# esp32.net
KiCad netlist of a schematic drawn in EAGLE
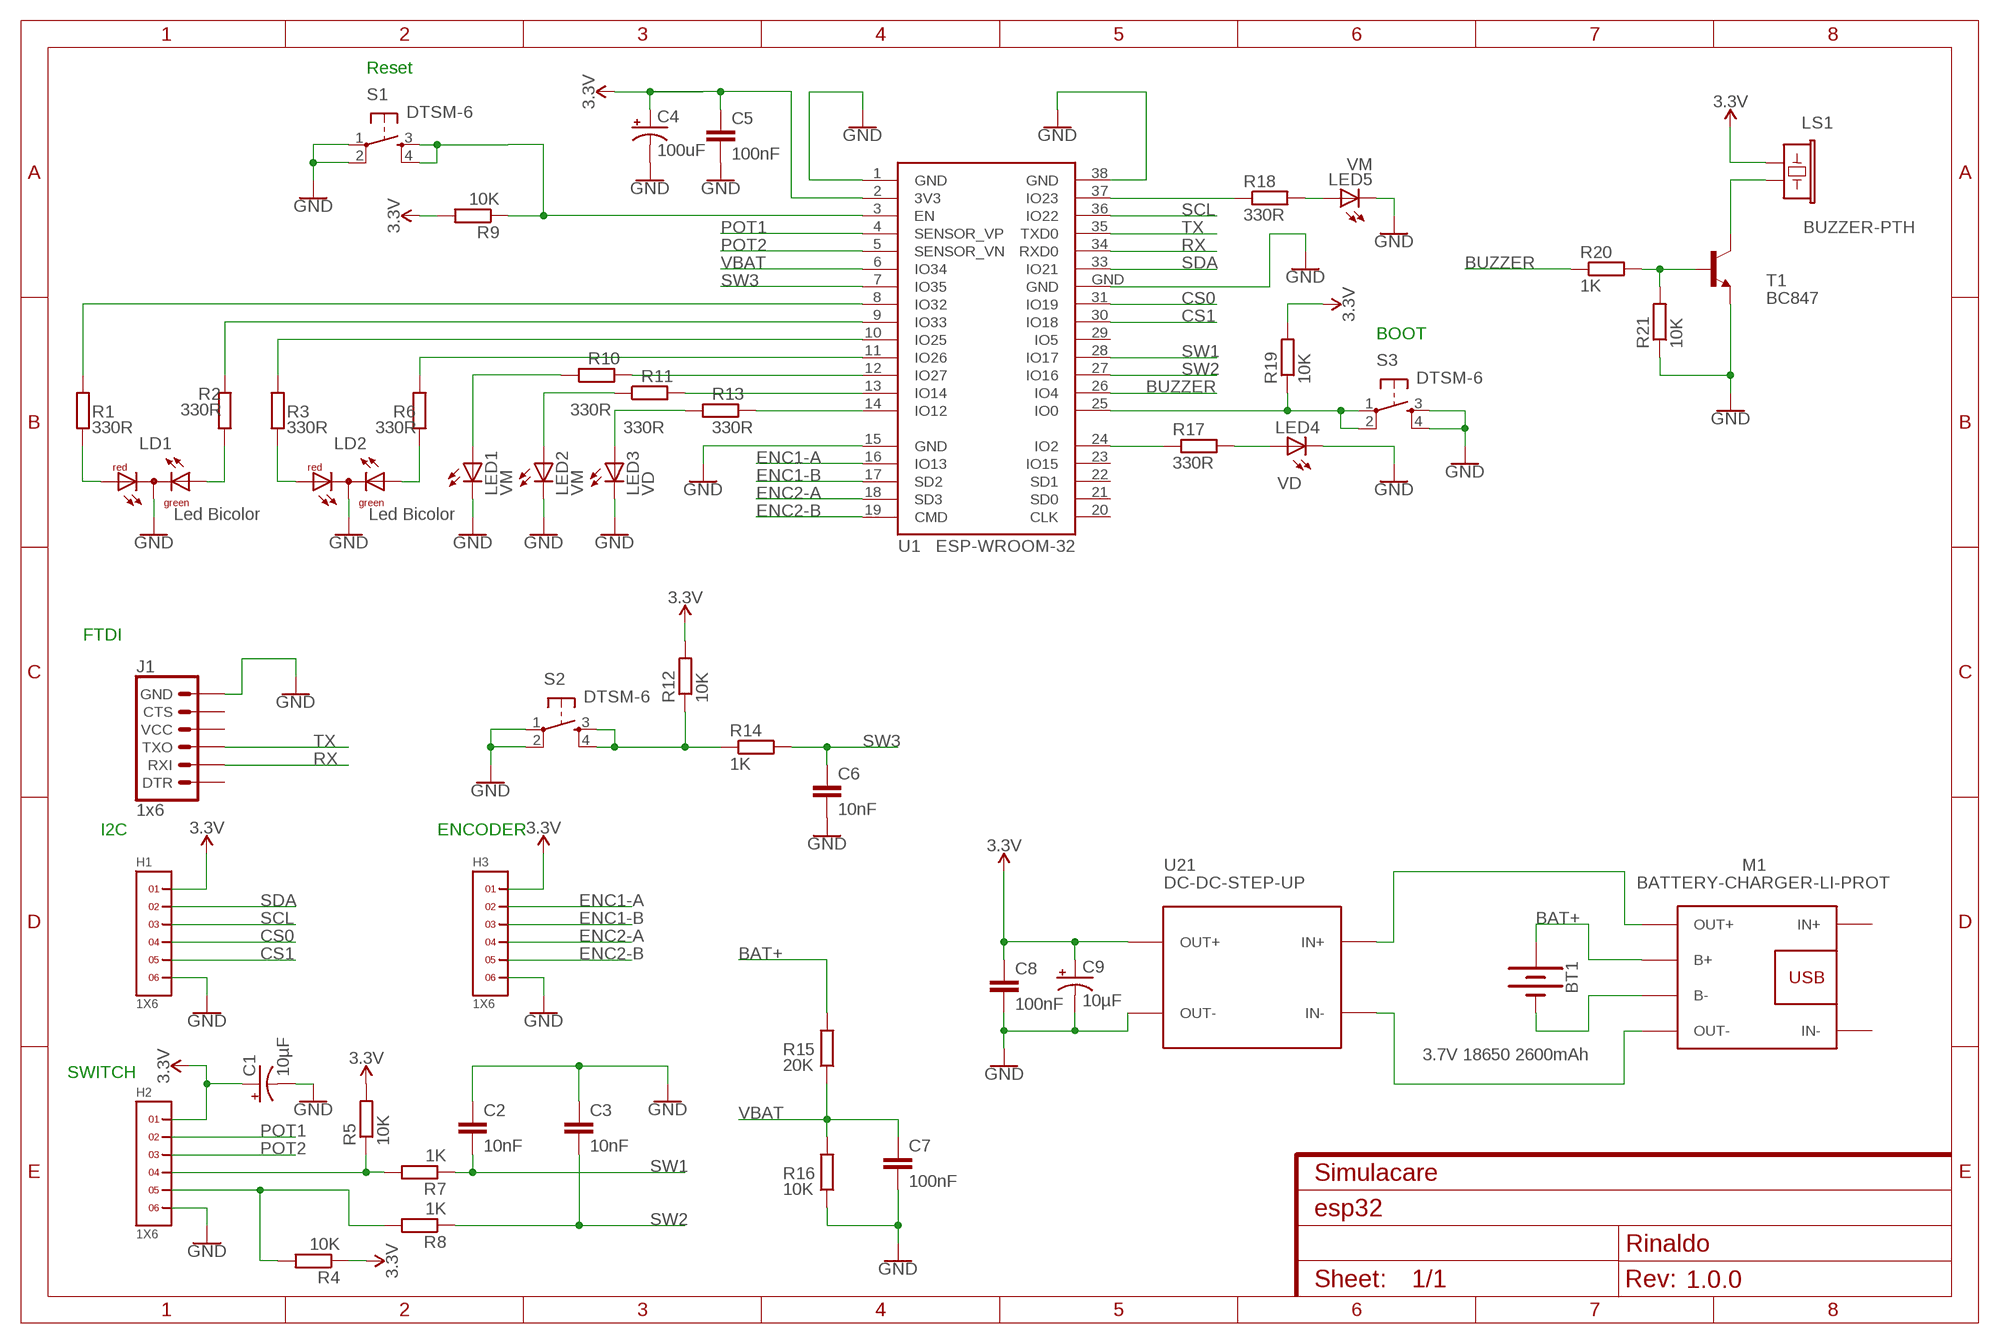
[diagram p0: schematic, sheet 1]

(export (version "E")
  (design (tool "Eeschema 10.0.6"))
  (components
    (comp (ref "BT1")
      (value "3.7V 18650 2600mAh")
      (footprint "eagle-import:BATTERY_18650-HOLDER")
      (libsource (lib "eagle-import") (part "BATTERY-18650"))
    )
    (comp (ref "C1")
      (value "10µF")
      (footprint "eagle-import:EIA6032-NOM")
      (libsource (lib "eagle-import") (part "10UF-POLAR-EIA6032-25V-10%"))
    )
    (comp (ref "C2")
      (value "10nF")
      (footprint "eagle-import:0603")
      (libsource (lib "eagle-import") (part "0.1UF-0603-25V-5%"))
    )
    (comp (ref "C3")
      (value "10nF")
      (footprint "eagle-import:0603")
      (libsource (lib "eagle-import") (part "0.1UF-0603-25V-5%"))
    )
    (comp (ref "C4")
      (value "100uF")
      (footprint "eagle-import:NIC_10X10.5_CAP")
      (libsource (lib "eagle-import") (part "100UF-POLAR-10X10.5-63V-20%"))
    )
    (comp (ref "C5")
      (value "100nF")
      (footprint "eagle-import:0603")
      (libsource (lib "eagle-import") (part "0.1UF-0603-25V-5%"))
    )
    (comp (ref "C6")
      (value "10nF")
      (footprint "eagle-import:0603")
      (libsource (lib "eagle-import") (part "0.1UF-0603-25V-5%"))
    )
    (comp (ref "C7")
      (value "100nF")
      (footprint "eagle-import:0603")
      (libsource (lib "eagle-import") (part "0.1UF-0603-25V-5%"))
    )
    (comp (ref "C8")
      (value "100nF")
      (footprint "eagle-import:0603")
      (libsource (lib "eagle-import") (part "0.1UF-0603-25V-5%"))
    )
    (comp (ref "C9")
      (value "10µF")
      (footprint "eagle-import:EIA6032-NOM")
      (libsource (lib "eagle-import") (part "10UF-POLAR-EIA6032-25V-10%"))
    )
    (comp (ref "H1")
      (value "1X6")
      (footprint "eagle-import:1X6")
      (libsource (lib "eagle-import") (part "1X6"))
    )
    (comp (ref "H2")
      (value "1X6")
      (footprint "eagle-import:1X6")
      (libsource (lib "eagle-import") (part "1X6"))
    )
    (comp (ref "H3")
      (value "1X6")
      (footprint "eagle-import:1X6")
      (libsource (lib "eagle-import") (part "1X6"))
    )
    (comp (ref "J1")
      (value "1x6")
      (footprint "eagle-import:6_PIN_SERIAL_TARGET_SIDE_W_SILK")
      (libsource (lib "eagle-import") (part "6_PIN_SERIAL_TARGETSILK"))
    )
    (comp (ref "LD1")
      (value "Led Bicolor")
      (footprint "eagle-import:DUOLED-C-5MM")
      (libsource (lib "eagle-import") (part "DUOLED-RG-C"))
    )
    (comp (ref "LD2")
      (value "Led Bicolor")
      (footprint "eagle-import:DUOLED-C-5MM")
      (libsource (lib "eagle-import") (part "DUOLED-RG-C"))
    )
    (comp (ref "LED1")
      (value "VM")
      (footprint "eagle-import:LED5MM")
      (libsource (lib "eagle-import") (part "LED5MM"))
    )
    (comp (ref "LED2")
      (value "VM")
      (footprint "eagle-import:LED5MM")
      (libsource (lib "eagle-import") (part "LED5MM"))
    )
    (comp (ref "LED3")
      (value "VD")
      (footprint "eagle-import:LED5MM")
      (libsource (lib "eagle-import") (part "LED5MM"))
    )
    (comp (ref "LED4")
      (value "VD")
      (footprint "eagle-import:LED5MM")
      (libsource (lib "eagle-import") (part "LED5MM"))
    )
    (comp (ref "LED5")
      (value "VM")
      (footprint "eagle-import:LED5MM")
      (libsource (lib "eagle-import") (part "LED5MM"))
    )
    (comp (ref "LS1")
      (value "BUZZER-PTH")
      (footprint "eagle-import:BUZZER-12MM")
      (libsource (lib "eagle-import") (part "BUZZER-PTH"))
    )
    (comp (ref "M1")
      (value "BATTERY-CHARGER-LI-PROT")
      (footprint "eagle-import:BATTERY-CHARGER-LI-PROT")
      (libsource (lib "eagle-import") (part "BATTERY-CHARGER-LI-PROT"))
    )
    (comp (ref "R1")
      (value "330R")
      (footprint "eagle-import:R0603")
      (libsource (lib "eagle-import") (part "R-EU_R0603"))
    )
    (comp (ref "R2")
      (value "330R")
      (footprint "eagle-import:R0603")
      (libsource (lib "eagle-import") (part "R-EU_R0603"))
    )
    (comp (ref "R3")
      (value "330R")
      (footprint "eagle-import:R0603")
      (libsource (lib "eagle-import") (part "R-EU_R0603"))
    )
    (comp (ref "R4")
      (value "10K")
      (footprint "eagle-import:R0603")
      (libsource (lib "eagle-import") (part "R-EU_R0603"))
    )
    (comp (ref "R5")
      (value "10K")
      (footprint "eagle-import:R0603")
      (libsource (lib "eagle-import") (part "R-EU_R0603"))
    )
    (comp (ref "R6")
      (value "330R")
      (footprint "eagle-import:R0603")
      (libsource (lib "eagle-import") (part "R-EU_R0603"))
    )
    (comp (ref "R7")
      (value "1K")
      (footprint "eagle-import:R0603")
      (libsource (lib "eagle-import") (part "R-EU_R0603"))
    )
    (comp (ref "R8")
      (value "1K")
      (footprint "eagle-import:R0603")
      (libsource (lib "eagle-import") (part "R-EU_R0603"))
    )
    (comp (ref "R9")
      (value "10K")
      (footprint "eagle-import:R0603")
      (libsource (lib "eagle-import") (part "R-EU_R0603"))
    )
    (comp (ref "R10")
      (value "330R")
      (footprint "eagle-import:R0603")
      (libsource (lib "eagle-import") (part "R-EU_R0603"))
    )
    (comp (ref "R11")
      (value "330R")
      (footprint "eagle-import:R0603")
      (libsource (lib "eagle-import") (part "R-EU_R0603"))
    )
    (comp (ref "R12")
      (value "10K")
      (footprint "eagle-import:R0603")
      (libsource (lib "eagle-import") (part "R-EU_R0603"))
    )
    (comp (ref "R13")
      (value "330R")
      (footprint "eagle-import:R0603")
      (libsource (lib "eagle-import") (part "R-EU_R0603"))
    )
    (comp (ref "R14")
      (value "1K")
      (footprint "eagle-import:R0603")
      (libsource (lib "eagle-import") (part "R-EU_R0603"))
    )
    (comp (ref "R15")
      (value "20K")
      (footprint "eagle-import:R0603")
      (libsource (lib "eagle-import") (part "R-EU_R0603"))
    )
    (comp (ref "R16")
      (value "10K")
      (footprint "eagle-import:R0603")
      (libsource (lib "eagle-import") (part "R-EU_R0603"))
    )
    (comp (ref "R17")
      (value "330R")
      (footprint "eagle-import:R0603")
      (libsource (lib "eagle-import") (part "R-EU_R0603"))
    )
    (comp (ref "R18")
      (value "330R")
      (footprint "eagle-import:R0603")
      (libsource (lib "eagle-import") (part "R-EU_R0603"))
    )
    (comp (ref "R19")
      (value "10K")
      (footprint "eagle-import:R0603")
      (libsource (lib "eagle-import") (part "R-EU_R0603"))
    )
    (comp (ref "R20")
      (value "1K")
      (footprint "eagle-import:R0603")
      (libsource (lib "eagle-import") (part "R-EU_R0603"))
    )
    (comp (ref "R21")
      (value "10K")
      (footprint "eagle-import:R0603")
      (libsource (lib "eagle-import") (part "R-EU_R0603"))
    )
    (comp (ref "S1")
      (value "DTSM-6")
      (footprint "eagle-import:DTSM-6")
      (libsource (lib "eagle-import") (part "DTSM-6"))
    )
    (comp (ref "S2")
      (value "DTSM-6")
      (footprint "eagle-import:DTSM-6")
      (libsource (lib "eagle-import") (part "DTSM-6"))
    )
    (comp (ref "S3")
      (value "DTSM-6")
      (footprint "eagle-import:DTSM-6")
      (libsource (lib "eagle-import") (part "DTSM-6"))
    )
    (comp (ref "T1")
      (value "BC847")
      (footprint "eagle-import:SOT23")
      (libsource (lib "eagle-import") (part "BC847"))
    )
    (comp (ref "U1")
      (value "ESP-WROOM-32")
      (footprint "eagle-import:ESP-WROOM-32")
      (libsource (lib "eagle-import") (part "ESP-WROOM-32"))
    )
    (comp (ref "U21")
      (value "DC-DC-STEP-UP")
      (footprint "eagle-import:DC-DC-STEP-UP-MT3608")
      (libsource (lib "eagle-import") (part "DC-DC-STEP-UP-MT3608"))
    )
  )
  (nets
    (net (code "1") (name "/BAT+") (class "Default")
      (node (ref "BT1") (pin "PWR@1") (pinfunction "+_PWR@1") (pintype "power_in"))
      (node (ref "M1") (pin "B+") (pinfunction "B+_B+") (pintype "bidirectional"))
      (node (ref "R15") (pin "2") (pinfunction "2_2") (pintype "passive"))
    )
    (net (code "2") (name "/BUZZER") (class "Default")
      (node (ref "R20") (pin "1") (pinfunction "1_1") (pintype "passive"))
      (node (ref "U1") (pin "26") (pinfunction "IO4_26") (pintype "bidirectional"))
    )
    (net (code "3") (name "/CS0") (class "Default")
      (node (ref "H1") (pin "4") (pinfunction "4_4") (pintype "bidirectional"))
      (node (ref "U1") (pin "31") (pinfunction "IO19_31") (pintype "bidirectional"))
    )
    (net (code "4") (name "/CS1") (class "Default")
      (node (ref "H1") (pin "5") (pinfunction "5_5") (pintype "bidirectional"))
      (node (ref "U1") (pin "30") (pinfunction "IO18_30") (pintype "bidirectional"))
    )
    (net (code "5") (name "/ENC1-A") (class "Default")
      (node (ref "H3") (pin "2") (pinfunction "2_2") (pintype "bidirectional"))
      (node (ref "U1") (pin "16") (pinfunction "IO13_16") (pintype "bidirectional"))
    )
    (net (code "6") (name "/ENC1-B") (class "Default")
      (node (ref "H3") (pin "3") (pinfunction "3_3") (pintype "bidirectional"))
      (node (ref "U1") (pin "17") (pinfunction "SD2_17") (pintype "bidirectional"))
    )
    (net (code "7") (name "/ENC2-A") (class "Default")
      (node (ref "H3") (pin "4") (pinfunction "4_4") (pintype "bidirectional"))
      (node (ref "U1") (pin "18") (pinfunction "SD3_18") (pintype "bidirectional"))
    )
    (net (code "8") (name "/ENC2-B") (class "Default")
      (node (ref "H3") (pin "5") (pinfunction "5_5") (pintype "bidirectional"))
      (node (ref "U1") (pin "19") (pinfunction "CMD_19") (pintype "bidirectional"))
    )
    (net (code "9") (name "/POT1") (class "Default")
      (node (ref "H2") (pin "2") (pinfunction "2_2") (pintype "bidirectional"))
      (node (ref "U1") (pin "4") (pinfunction "SENSOR_VP_4") (pintype "bidirectional"))
    )
    (net (code "10") (name "/POT2") (class "Default")
      (node (ref "H2") (pin "3") (pinfunction "3_3") (pintype "bidirectional"))
      (node (ref "U1") (pin "5") (pinfunction "SENSOR_VN_5") (pintype "bidirectional"))
    )
    (net (code "11") (name "/RX") (class "Default")
      (node (ref "J1") (pin "P$3") (pinfunction "RXI_P$3") (pintype "passive"))
      (node (ref "U1") (pin "34") (pinfunction "RXD0_34") (pintype "bidirectional"))
    )
    (net (code "12") (name "/SCL") (class "Default")
      (node (ref "H1") (pin "3") (pinfunction "3_3") (pintype "bidirectional"))
      (node (ref "U1") (pin "36") (pinfunction "IO22_36") (pintype "bidirectional"))
    )
    (net (code "13") (name "/SDA") (class "Default")
      (node (ref "H1") (pin "2") (pinfunction "2_2") (pintype "bidirectional"))
      (node (ref "U1") (pin "33") (pinfunction "IO21_33") (pintype "bidirectional"))
    )
    (net (code "14") (name "/SW1") (class "Default")
      (node (ref "C2") (pin "2") (pinfunction "2_2") (pintype "passive"))
      (node (ref "R7") (pin "1") (pinfunction "1_1") (pintype "passive"))
      (node (ref "U1") (pin "28") (pinfunction "IO17_28") (pintype "bidirectional"))
    )
    (net (code "15") (name "/SW2") (class "Default")
      (node (ref "C3") (pin "2") (pinfunction "2_2") (pintype "passive"))
      (node (ref "R8") (pin "1") (pinfunction "1_1") (pintype "passive"))
      (node (ref "U1") (pin "27") (pinfunction "IO16_27") (pintype "bidirectional"))
    )
    (net (code "16") (name "/SW3") (class "Default")
      (node (ref "C6") (pin "1") (pinfunction "1_1") (pintype "passive"))
      (node (ref "R14") (pin "2") (pinfunction "2_2") (pintype "passive"))
      (node (ref "U1") (pin "7") (pinfunction "IO35_7") (pintype "bidirectional"))
    )
    (net (code "17") (name "/TX") (class "Default")
      (node (ref "J1") (pin "P$2") (pinfunction "TXO_P$2") (pintype "passive"))
      (node (ref "U1") (pin "35") (pinfunction "TXD0_35") (pintype "bidirectional"))
    )
    (net (code "18") (name "/VBAT") (class "Default")
      (node (ref "C7") (pin "1") (pinfunction "1_1") (pintype "passive"))
      (node (ref "R15") (pin "1") (pinfunction "1_1") (pintype "passive"))
      (node (ref "R16") (pin "2") (pinfunction "2_2") (pintype "passive"))
      (node (ref "U1") (pin "6") (pinfunction "IO34_6") (pintype "bidirectional"))
    )
    (net (code "19") (name "3.3V") (class "Default")
      (node (ref "C1") (pin "A") (pinfunction "+_A") (pintype "passive"))
      (node (ref "C4") (pin "+") (pinfunction "+_+") (pintype "passive"))
      (node (ref "C5") (pin "1") (pinfunction "1_1") (pintype "passive"))
      (node (ref "C8") (pin "1") (pinfunction "1_1") (pintype "passive"))
      (node (ref "C9") (pin "A") (pinfunction "+_A") (pintype "passive"))
      (node (ref "H1") (pin "1") (pinfunction "1_1") (pintype "bidirectional"))
      (node (ref "H2") (pin "1") (pinfunction "1_1") (pintype "bidirectional"))
      (node (ref "H3") (pin "1") (pinfunction "1_1") (pintype "bidirectional"))
      (node (ref "LS1") (pin "+") (pinfunction "1_+") (pintype "passive"))
      (node (ref "R12") (pin "2") (pinfunction "2_2") (pintype "passive"))
      (node (ref "R19") (pin "2") (pinfunction "2_2") (pintype "passive"))
      (node (ref "R4") (pin "1") (pinfunction "1_1") (pintype "passive"))
      (node (ref "R5") (pin "2") (pinfunction "2_2") (pintype "passive"))
      (node (ref "R9") (pin "2") (pinfunction "2_2") (pintype "passive"))
      (node (ref "U1") (pin "2") (pinfunction "3V3_2") (pintype "power_in"))
      (node (ref "U21") (pin "OUT+") (pinfunction "OUT+_OUT+") (pintype "bidirectional"))
    )
    (net (code "20") (name "GND") (class "Default")
      (node (ref "C1") (pin "C") (pinfunction "-_C") (pintype "passive"))
      (node (ref "C2") (pin "1") (pinfunction "1_1") (pintype "passive"))
      (node (ref "C3") (pin "1") (pinfunction "1_1") (pintype "passive"))
      (node (ref "C4") (pin "-") (pinfunction "-_-") (pintype "passive"))
      (node (ref "C5") (pin "2") (pinfunction "2_2") (pintype "passive"))
      (node (ref "C6") (pin "2") (pinfunction "2_2") (pintype "passive"))
      (node (ref "C7") (pin "2") (pinfunction "2_2") (pintype "passive"))
      (node (ref "C8") (pin "2") (pinfunction "2_2") (pintype "passive"))
      (node (ref "C9") (pin "C") (pinfunction "-_C") (pintype "passive"))
      (node (ref "H1") (pin "6") (pinfunction "6_6") (pintype "bidirectional"))
      (node (ref "H2") (pin "6") (pinfunction "6_6") (pintype "bidirectional"))
      (node (ref "H3") (pin "6") (pinfunction "6_6") (pintype "bidirectional"))
      (node (ref "J1") (pin "P$6") (pinfunction "GND_P$6") (pintype "passive"))
      (node (ref "LD1") (pin "C") (pinfunction "C_C") (pintype "passive"))
      (node (ref "LD2") (pin "C") (pinfunction "C_C") (pintype "passive"))
      (node (ref "LED1") (pin "K") (pinfunction "C_K") (pintype "passive"))
      (node (ref "LED2") (pin "K") (pinfunction "C_K") (pintype "passive"))
      (node (ref "LED3") (pin "K") (pinfunction "C_K") (pintype "passive"))
      (node (ref "LED4") (pin "K") (pinfunction "C_K") (pintype "passive"))
      (node (ref "LED5") (pin "K") (pinfunction "C_K") (pintype "passive"))
      (node (ref "R16") (pin "1") (pinfunction "1_1") (pintype "passive"))
      (node (ref "R21") (pin "1") (pinfunction "1_1") (pintype "passive"))
      (node (ref "S1") (pin "1") (pinfunction "1_1") (pintype "passive"))
      (node (ref "S1") (pin "2") (pinfunction "2_2") (pintype "passive"))
      (node (ref "S2") (pin "1") (pinfunction "1_1") (pintype "passive"))
      (node (ref "S2") (pin "2") (pinfunction "2_2") (pintype "passive"))
      (node (ref "S3") (pin "3") (pinfunction "3_3") (pintype "passive"))
      (node (ref "S3") (pin "4") (pinfunction "4_4") (pintype "passive"))
      (node (ref "T1") (pin "2") (pinfunction "E_2") (pintype "passive"))
      (node (ref "U1") (pin "1") (pinfunction "GND_1") (pintype "power_in"))
      (node (ref "U1") (pin "15") (pinfunction "GND_15") (pintype "power_in"))
      (node (ref "U1") (pin "38") (pinfunction "GND_38") (pintype "power_in"))
      (node (ref "U1") (pin "GND") (pinfunction "GND_GND") (pintype "power_in"))
      (node (ref "U21") (pin "OUT-") (pinfunction "OUT-_OUT-") (pintype "bidirectional"))
    )
    (net (code "21") (name "Net-(BT1--)") (class "Default")
      (node (ref "BT1") (pin "GND@1") (pinfunction "-_GND@1") (pintype "power_in"))
      (node (ref "M1") (pin "B-") (pinfunction "B-_B-") (pintype "bidirectional"))
    )
    (net (code "22") (name "Net-(H2-Pad4)") (class "Default")
      (node (ref "H2") (pin "4") (pinfunction "4_4") (pintype "bidirectional"))
      (node (ref "R5") (pin "1") (pinfunction "1_1") (pintype "passive"))
      (node (ref "R7") (pin "2") (pinfunction "2_2") (pintype "passive"))
    )
    (net (code "23") (name "Net-(H2-Pad5)") (class "Default")
      (node (ref "H2") (pin "5") (pinfunction "5_5") (pintype "bidirectional"))
      (node (ref "R4") (pin "2") (pinfunction "2_2") (pintype "passive"))
      (node (ref "R8") (pin "2") (pinfunction "2_2") (pintype "passive"))
    )
    (net (code "24") (name "Net-(LD1-AG)") (class "Default")
      (node (ref "LD1") (pin "AX") (pinfunction "AG_AX") (pintype "passive"))
      (node (ref "R2") (pin "1") (pinfunction "1_1") (pintype "passive"))
    )
    (net (code "25") (name "Net-(LD1-PadAR)") (class "Default")
      (node (ref "LD1") (pin "AR") (pinfunction "AR_AR") (pintype "passive"))
      (node (ref "R1") (pin "1") (pinfunction "1_1") (pintype "passive"))
    )
    (net (code "26") (name "Net-(LD2-AG)") (class "Default")
      (node (ref "LD2") (pin "AX") (pinfunction "AG_AX") (pintype "passive"))
      (node (ref "R6") (pin "1") (pinfunction "1_1") (pintype "passive"))
    )
    (net (code "27") (name "Net-(LD2-PadAR)") (class "Default")
      (node (ref "LD2") (pin "AR") (pinfunction "AR_AR") (pintype "passive"))
      (node (ref "R3") (pin "1") (pinfunction "1_1") (pintype "passive"))
    )
    (net (code "28") (name "Net-(LED1-PadA)") (class "Default")
      (node (ref "LED1") (pin "A") (pinfunction "A_A") (pintype "passive"))
      (node (ref "R10") (pin "1") (pinfunction "1_1") (pintype "passive"))
    )
    (net (code "29") (name "Net-(LED2-PadA)") (class "Default")
      (node (ref "LED2") (pin "A") (pinfunction "A_A") (pintype "passive"))
      (node (ref "R11") (pin "1") (pinfunction "1_1") (pintype "passive"))
    )
    (net (code "30") (name "Net-(LED3-PadA)") (class "Default")
      (node (ref "LED3") (pin "A") (pinfunction "A_A") (pintype "passive"))
      (node (ref "R13") (pin "1") (pinfunction "1_1") (pintype "passive"))
    )
    (net (code "31") (name "Net-(LED4-PadA)") (class "Default")
      (node (ref "LED4") (pin "A") (pinfunction "A_A") (pintype "passive"))
      (node (ref "R17") (pin "2") (pinfunction "2_2") (pintype "passive"))
    )
    (net (code "32") (name "Net-(LED5-PadA)") (class "Default")
      (node (ref "LED5") (pin "A") (pinfunction "A_A") (pintype "passive"))
      (node (ref "R18") (pin "2") (pinfunction "2_2") (pintype "passive"))
    )
    (net (code "33") (name "Net-(LS1-2)") (class "Default")
      (node (ref "LS1") (pin "-") (pinfunction "2_-") (pintype "passive"))
      (node (ref "T1") (pin "3") (pinfunction "C_3") (pintype "passive"))
    )
    (net (code "34") (name "Net-(M1-PadOUT+)") (class "Default")
      (node (ref "M1") (pin "OUT+") (pinfunction "OUT+_OUT+") (pintype "bidirectional"))
      (node (ref "U21") (pin "IN+") (pinfunction "IN+_IN+") (pintype "bidirectional"))
    )
    (net (code "35") (name "Net-(M1-PadOUT-)") (class "Default")
      (node (ref "M1") (pin "OUT-") (pinfunction "OUT-_OUT-") (pintype "bidirectional"))
      (node (ref "U21") (pin "IN-") (pinfunction "IN-_IN-") (pintype "bidirectional"))
    )
    (net (code "36") (name "Net-(R12-Pad1)") (class "Default")
      (node (ref "R12") (pin "1") (pinfunction "1_1") (pintype "passive"))
      (node (ref "R14") (pin "1") (pinfunction "1_1") (pintype "passive"))
      (node (ref "S2") (pin "3") (pinfunction "3_3") (pintype "passive"))
      (node (ref "S2") (pin "4") (pinfunction "4_4") (pintype "passive"))
    )
    (net (code "37") (name "Net-(T1-B)") (class "Default")
      (node (ref "R20") (pin "2") (pinfunction "2_2") (pintype "passive"))
      (node (ref "R21") (pin "2") (pinfunction "2_2") (pintype "passive"))
      (node (ref "T1") (pin "1") (pinfunction "B_1") (pintype "passive"))
    )
    (net (code "38") (name "Net-(U1-EN)") (class "Default")
      (node (ref "R9") (pin "1") (pinfunction "1_1") (pintype "passive"))
      (node (ref "S1") (pin "3") (pinfunction "3_3") (pintype "passive"))
      (node (ref "S1") (pin "4") (pinfunction "4_4") (pintype "passive"))
      (node (ref "U1") (pin "3") (pinfunction "EN_3") (pintype "input"))
    )
    (net (code "39") (name "Net-(U1-IO0)") (class "Default")
      (node (ref "R19") (pin "1") (pinfunction "1_1") (pintype "passive"))
      (node (ref "S3") (pin "1") (pinfunction "1_1") (pintype "passive"))
      (node (ref "S3") (pin "2") (pinfunction "2_2") (pintype "passive"))
      (node (ref "U1") (pin "25") (pinfunction "IO0_25") (pintype "bidirectional"))
    )
    (net (code "40") (name "Net-(U1-IO2)") (class "Default")
      (node (ref "R17") (pin "1") (pinfunction "1_1") (pintype "passive"))
      (node (ref "U1") (pin "24") (pinfunction "IO2_24") (pintype "bidirectional"))
    )
    (net (code "41") (name "Net-(U1-IO12)") (class "Default")
      (node (ref "R13") (pin "2") (pinfunction "2_2") (pintype "passive"))
      (node (ref "U1") (pin "14") (pinfunction "IO12_14") (pintype "bidirectional"))
    )
    (net (code "42") (name "Net-(U1-IO14)") (class "Default")
      (node (ref "R11") (pin "2") (pinfunction "2_2") (pintype "passive"))
      (node (ref "U1") (pin "13") (pinfunction "IO14_13") (pintype "bidirectional"))
    )
    (net (code "43") (name "Net-(U1-IO23)") (class "Default")
      (node (ref "R18") (pin "1") (pinfunction "1_1") (pintype "passive"))
      (node (ref "U1") (pin "37") (pinfunction "IO23_37") (pintype "bidirectional"))
    )
    (net (code "44") (name "Net-(U1-IO25)") (class "Default")
      (node (ref "R3") (pin "2") (pinfunction "2_2") (pintype "passive"))
      (node (ref "U1") (pin "10") (pinfunction "IO25_10") (pintype "bidirectional"))
    )
    (net (code "45") (name "Net-(U1-IO26)") (class "Default")
      (node (ref "R6") (pin "2") (pinfunction "2_2") (pintype "passive"))
      (node (ref "U1") (pin "11") (pinfunction "IO26_11") (pintype "bidirectional"))
    )
    (net (code "46") (name "Net-(U1-IO27)") (class "Default")
      (node (ref "R10") (pin "2") (pinfunction "2_2") (pintype "passive"))
      (node (ref "U1") (pin "12") (pinfunction "IO27_12") (pintype "bidirectional"))
    )
    (net (code "47") (name "Net-(U1-IO32)") (class "Default")
      (node (ref "R1") (pin "2") (pinfunction "2_2") (pintype "passive"))
      (node (ref "U1") (pin "8") (pinfunction "IO32_8") (pintype "bidirectional"))
    )
    (net (code "48") (name "Net-(U1-IO33)") (class "Default")
      (node (ref "R2") (pin "2") (pinfunction "2_2") (pintype "passive"))
      (node (ref "U1") (pin "9") (pinfunction "IO33_9") (pintype "bidirectional"))
    )
    (net (code "49") (name "unconnected-(J1-CTS-PadP$5)") (class "Default")
      (node (ref "J1") (pin "P$5") (pinfunction "CTS_P$5") (pintype "passive"))
    )
    (net (code "50") (name "unconnected-(J1-DTR-PadP$1)") (class "Default")
      (node (ref "J1") (pin "P$1") (pinfunction "DTR_P$1") (pintype "passive"))
    )
    (net (code "51") (name "unconnected-(J1-VCC-PadP$4)") (class "Default")
      (node (ref "J1") (pin "P$4") (pinfunction "VCC_P$4") (pintype "passive"))
    )
    (net (code "52") (name "unconnected-(M1-PadIN+)") (class "Default")
      (node (ref "M1") (pin "IN+") (pinfunction "IN+_IN+") (pintype "bidirectional"))
    )
    (net (code "53") (name "unconnected-(M1-PadIN-)") (class "Default")
      (node (ref "M1") (pin "IN-") (pinfunction "IN-_IN-") (pintype "bidirectional"))
    )
    (net (code "54") (name "unconnected-(U1-CLK-Pad20)") (class "Default")
      (node (ref "U1") (pin "20") (pinfunction "CLK_20") (pintype "bidirectional"))
    )
    (net (code "55") (name "unconnected-(U1-IO5-Pad29)") (class "Default")
      (node (ref "U1") (pin "29") (pinfunction "IO5_29") (pintype "bidirectional"))
    )
    (net (code "56") (name "unconnected-(U1-IO15-Pad23)") (class "Default")
      (node (ref "U1") (pin "23") (pinfunction "IO15_23") (pintype "bidirectional"))
    )
    (net (code "57") (name "unconnected-(U1-SD0-Pad21)") (class "Default")
      (node (ref "U1") (pin "21") (pinfunction "SD0_21") (pintype "bidirectional"))
    )
    (net (code "58") (name "unconnected-(U1-SD1-Pad22)") (class "Default")
      (node (ref "U1") (pin "22") (pinfunction "SD1_22") (pintype "bidirectional"))
    )
  )
)
